# 10_ToSourceBoard.net
KiCad netlist of a schematic drawn in Altium Designer
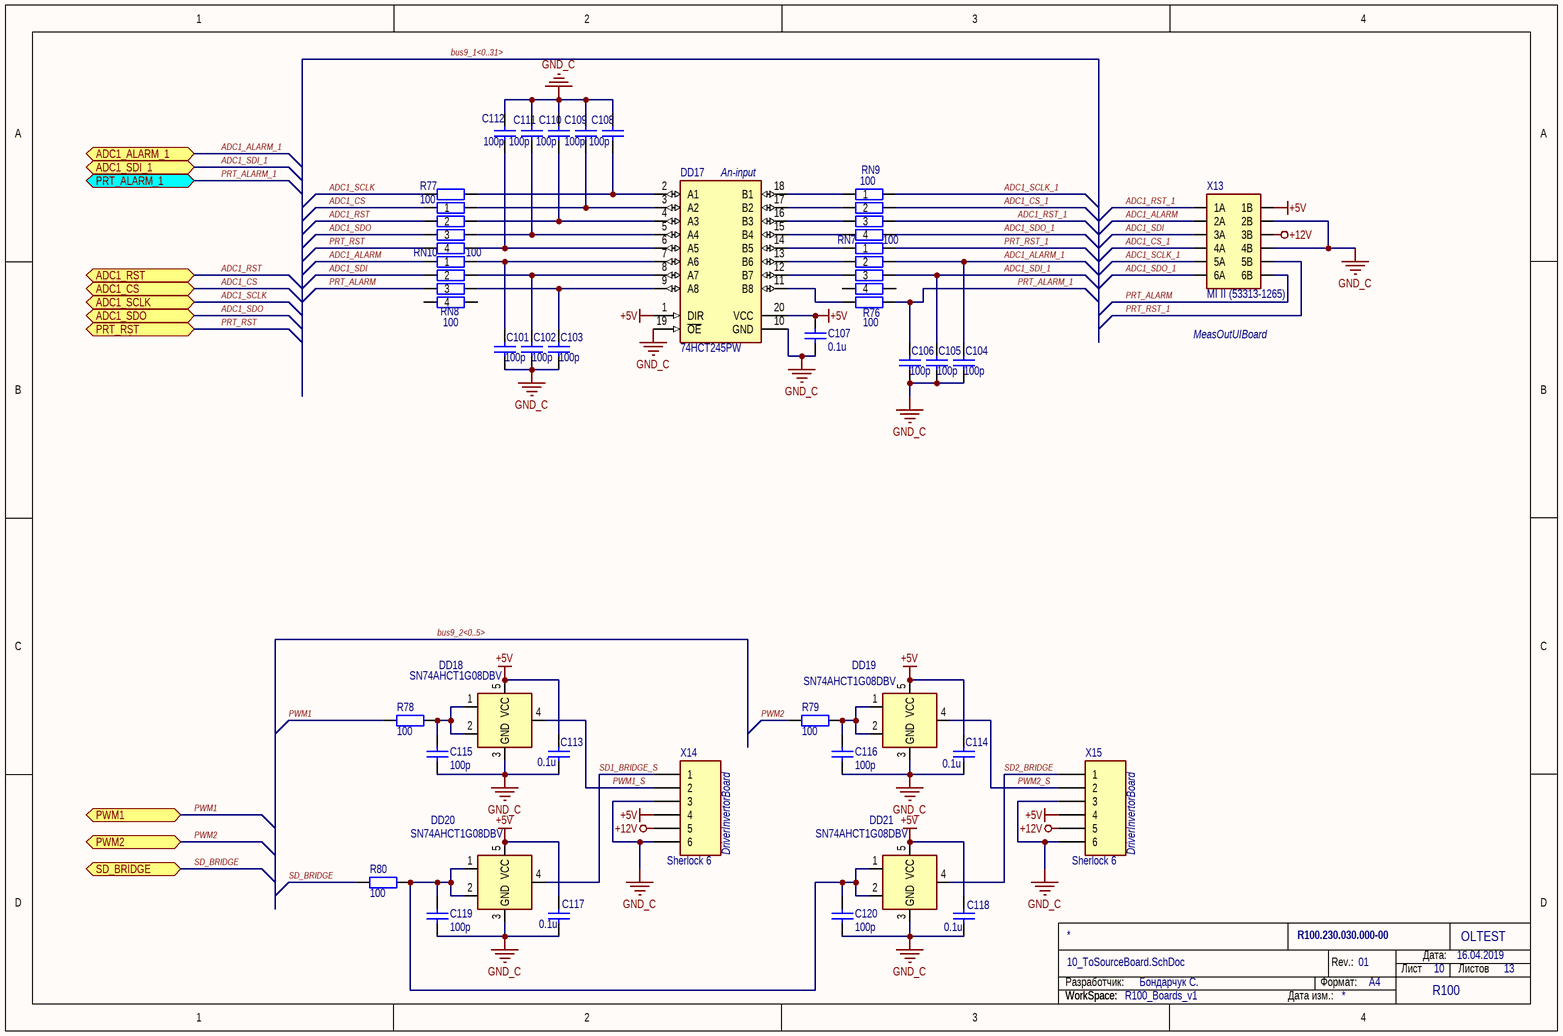
[diagram p0: 10_ToSourceBoard.SchDoc]

(export (version "E")
  (design (tool "Eeschema 10.0.6"))
  (components
    (comp (ref "C101")
      (value "100p")
      (footprint "mainLib:SMD_C_0603")
      (description "SMD C 0603 MURATA 100V 5% NP0")
      (fields (field (name "PARTNUMBER") "GRM1885C2A101JA01") (field (name "MANUFACTURER") "MURATA"))
      (libsource (lib "mainRCLib") (part "C0603 100p 100V 5%"))
    )
    (comp (ref "C102")
      (value "100p")
      (footprint "mainLib:SMD_C_0603")
      (description "SMD C 0603 MURATA 100V 5% NP0")
      (fields (field (name "PARTNUMBER") "GRM1885C2A101JA01") (field (name "MANUFACTURER") "MURATA"))
      (libsource (lib "mainRCLib") (part "C0603 100p 100V 5%"))
    )
    (comp (ref "C103")
      (value "100p")
      (footprint "mainLib:SMD_C_0603")
      (description "SMD C 0603 MURATA 100V 5% NP0")
      (fields (field (name "PARTNUMBER") "GRM1885C2A101JA01") (field (name "MANUFACTURER") "MURATA"))
      (libsource (lib "mainRCLib") (part "C0603 100p 100V 5%"))
    )
    (comp (ref "C104")
      (value "100p")
      (footprint "mainLib:SMD_C_0603")
      (description "SMD C 0603 MURATA 100V 5% NP0")
      (fields (field (name "PARTNUMBER") "GRM1885C2A101JA01") (field (name "MANUFACTURER") "MURATA"))
      (libsource (lib "mainRCLib") (part "C0603 100p 100V 5%"))
    )
    (comp (ref "C105")
      (value "100p")
      (footprint "mainLib:SMD_C_0603")
      (description "SMD C 0603 MURATA 100V 5% NP0")
      (fields (field (name "PARTNUMBER") "GRM1885C2A101JA01") (field (name "MANUFACTURER") "MURATA"))
      (libsource (lib "mainRCLib") (part "C0603 100p 100V 5%"))
    )
    (comp (ref "C106")
      (value "100p")
      (footprint "mainLib:SMD_C_0603")
      (description "SMD C 0603 MURATA 100V 5% NP0")
      (fields (field (name "PARTNUMBER") "GRM1885C2A101JA01") (field (name "MANUFACTURER") "MURATA"))
      (libsource (lib "mainRCLib") (part "C0603 100p 100V 5%"))
    )
    (comp (ref "C107")
      (value "0.1u")
      (footprint "mainLib:SMD_C_0603")
      (description "SMD C 0603 MURATA 50V 10% X7R")
      (fields (field (name "PARTNUMBER") "GRM188R71H104K") (field (name "MANUFACTURER") "MURATA"))
      (libsource (lib "mainRCLib") (part "C0603 0.1u 50V 10%"))
    )
    (comp (ref "C108")
      (value "100p")
      (footprint "mainLib:SMD_C_0603")
      (description "SMD C 0603 MURATA 100V 5% NP0")
      (fields (field (name "PARTNUMBER") "GRM1885C2A101JA01") (field (name "MANUFACTURER") "MURATA"))
      (libsource (lib "mainRCLib") (part "C0603 100p 100V 5%"))
    )
    (comp (ref "C109")
      (value "100p")
      (footprint "mainLib:SMD_C_0603")
      (description "SMD C 0603 MURATA 100V 5% NP0")
      (fields (field (name "PARTNUMBER") "GRM1885C2A101JA01") (field (name "MANUFACTURER") "MURATA"))
      (libsource (lib "mainRCLib") (part "C0603 100p 100V 5%"))
    )
    (comp (ref "C110")
      (value "100p")
      (footprint "mainLib:SMD_C_0603")
      (description "SMD C 0603 MURATA 100V 5% NP0")
      (fields (field (name "PARTNUMBER") "GRM1885C2A101JA01") (field (name "MANUFACTURER") "MURATA"))
      (libsource (lib "mainRCLib") (part "C0603 100p 100V 5%"))
    )
    (comp (ref "C111")
      (value "100p")
      (footprint "mainLib:SMD_C_0603")
      (description "SMD C 0603 MURATA 100V 5% NP0")
      (fields (field (name "PARTNUMBER") "GRM1885C2A101JA01") (field (name "MANUFACTURER") "MURATA"))
      (libsource (lib "mainRCLib") (part "C0603 100p 100V 5%"))
    )
    (comp (ref "C112")
      (value "100p")
      (footprint "mainLib:SMD_C_0603")
      (description "SMD C 0603 MURATA 100V 5% NP0")
      (fields (field (name "PARTNUMBER") "GRM1885C2A101JA01") (field (name "MANUFACTURER") "MURATA"))
      (libsource (lib "mainRCLib") (part "C0603 100p 100V 5%"))
    )
    (comp (ref "C113")
      (value "0.1u")
      (footprint "mainLib:SMD_C_0603")
      (description "SMD C 0603 MURATA 50V 10% X7R")
      (fields (field (name "PARTNUMBER") "GRM188R71H104K") (field (name "MANUFACTURER") "MURATA"))
      (libsource (lib "mainRCLib") (part "C0603 0.1u 50V 10%"))
    )
    (comp (ref "C114")
      (value "0.1u")
      (footprint "mainLib:SMD_C_0603")
      (description "SMD C 0603 MURATA 50V 10% X7R")
      (fields (field (name "PARTNUMBER") "GRM188R71H104K") (field (name "MANUFACTURER") "MURATA"))
      (libsource (lib "mainRCLib") (part "C0603 0.1u 50V 10%"))
    )
    (comp (ref "C115")
      (value "100p")
      (footprint "mainLib:SMD_C_0603")
      (description "SMD C 0603 MURATA 100V 5% NP0")
      (fields (field (name "PARTNUMBER") "GRM1885C2A101JA01") (field (name "MANUFACTURER") "MURATA"))
      (libsource (lib "mainRCLib") (part "C0603 100p 100V 5%"))
    )
    (comp (ref "C116")
      (value "100p")
      (footprint "mainLib:SMD_C_0603")
      (description "SMD C 0603 MURATA 100V 5% NP0")
      (fields (field (name "PARTNUMBER") "GRM1885C2A101JA01") (field (name "MANUFACTURER") "MURATA"))
      (libsource (lib "mainRCLib") (part "C0603 100p 100V 5%"))
    )
    (comp (ref "C117")
      (value "0.1u")
      (footprint "mainLib:SMD_C_0603")
      (description "SMD C 0603 MURATA 50V 10% X7R")
      (fields (field (name "PARTNUMBER") "GRM188R71H104K") (field (name "MANUFACTURER") "MURATA"))
      (libsource (lib "mainRCLib") (part "C0603 0.1u 50V 10%"))
    )
    (comp (ref "C118")
      (value "0.1u")
      (footprint "mainLib:SMD_C_0603")
      (description "SMD C 0603 MURATA 50V 10% X7R")
      (fields (field (name "PARTNUMBER") "GRM188R71H104K") (field (name "MANUFACTURER") "MURATA"))
      (libsource (lib "mainRCLib") (part "C0603 0.1u 50V 10%"))
    )
    (comp (ref "C119")
      (value "100p")
      (footprint "mainLib:SMD_C_0603")
      (description "SMD C 0603 MURATA 100V 5% NP0")
      (fields (field (name "PARTNUMBER") "GRM1885C2A101JA01") (field (name "MANUFACTURER") "MURATA"))
      (libsource (lib "mainRCLib") (part "C0603 100p 100V 5%"))
    )
    (comp (ref "C120")
      (value "100p")
      (footprint "mainLib:SMD_C_0603")
      (description "SMD C 0603 MURATA 100V 5% NP0")
      (fields (field (name "PARTNUMBER") "GRM1885C2A101JA01") (field (name "MANUFACTURER") "MURATA"))
      (libsource (lib "mainRCLib") (part "C0603 100p 100V 5%"))
    )
    (comp (ref "DD17")
      (value "74HCT245PW")
      (footprint "mainLib:PW0020A_M")
      (description "Octal Bus Transceivers With 3-State Outputs, PW0020A")
      (fields (field (name "MANUFACTURER") "NXP"))
      (libsource (lib "mainLib") (part "74HCT245PW"))
    )
    (comp (ref "DD18")
      (value "SN74AHCT1G08DBV")
      (footprint "mainLib:SOT-23(DBV)")
      (description "2-in AND")
      (fields (field (name "MANUFACTURER") "Texas Instruments"))
      (libsource (lib "mainLib") (part "SN74AHCT1G08DBV"))
    )
    (comp (ref "DD19")
      (value "SN74AHCT1G08DBV")
      (footprint "mainLib:SOT-23(DBV)")
      (description "2-in AND")
      (fields (field (name "MANUFACTURER") "Texas Instruments"))
      (libsource (lib "mainLib") (part "SN74AHCT1G08DBV"))
    )
    (comp (ref "DD20")
      (value "SN74AHCT1G08DBV")
      (footprint "mainLib:SOT-23(DBV)")
      (description "2-in AND")
      (fields (field (name "MANUFACTURER") "Texas Instruments"))
      (libsource (lib "mainLib") (part "SN74AHCT1G08DBV"))
    )
    (comp (ref "DD21")
      (value "SN74AHCT1G08DBV")
      (footprint "mainLib:SOT-23(DBV)")
      (description "2-in AND")
      (fields (field (name "MANUFACTURER") "Texas Instruments"))
      (libsource (lib "mainLib") (part "SN74AHCT1G08DBV"))
    )
    (comp (ref "R76")
      (value "100")
      (footprint "SMD_R_0603")
      (description "SMD R 0603 VISHAY 0.1W 75V 1% 100ppm")
      (fields (field (name "PARTNUMBER") "CRCW0603100RFK") (field (name "MANUFACTURER") "VISHAY"))
      (libsource (lib "mainRCLib") (part "R0603 100 1%"))
    )
    (comp (ref "R77")
      (value "100")
      (footprint "SMD_R_0603")
      (description "SMD R 0603 VISHAY 0.1W 75V 1% 100ppm")
      (fields (field (name "PARTNUMBER") "CRCW0603100RFK") (field (name "MANUFACTURER") "VISHAY"))
      (libsource (lib "mainRCLib") (part "R0603 100 1%"))
    )
    (comp (ref "R78")
      (value "100")
      (footprint "SMD_R_0603")
      (description "SMD R 0603 VISHAY 0.1W 75V 1% 100ppm")
      (fields (field (name "PARTNUMBER") "CRCW0603100RFK") (field (name "MANUFACTURER") "VISHAY"))
      (libsource (lib "mainRCLib") (part "R0603 100 1%"))
    )
    (comp (ref "R79")
      (value "100")
      (footprint "SMD_R_0603")
      (description "SMD R 0603 VISHAY 0.1W 75V 1% 100ppm")
      (fields (field (name "PARTNUMBER") "CRCW0603100RFK") (field (name "MANUFACTURER") "VISHAY"))
      (libsource (lib "mainRCLib") (part "R0603 100 1%"))
    )
    (comp (ref "R80")
      (value "100")
      (footprint "SMD_R_0603")
      (description "SMD R 0603 VISHAY 0.1W 75V 1% 100ppm")
      (fields (field (name "PARTNUMBER") "CRCW0603100RFK") (field (name "MANUFACTURER") "VISHAY"))
      (libsource (lib "mainRCLib") (part "R0603 100 1%"))
    )
    (comp (ref "RN7")
      (value "100")
      (footprint "mainLib:CRA06S")
      (description "SMD RESISTOR ARRAY VISHAY 0.063W 50V 1% 100ppm")
      (fields (field (name "PARTNUMBER") "CRA06S083100RF") (field (name "MANUFACTURER") "VISHAY"))
      (libsource (lib "mainRCLib") (part "CRA06S 4x100 1%"))
    )
    (comp (ref "RN8")
      (value "100")
      (footprint "mainLib:CRA06S")
      (description "SMD RESISTOR ARRAY VISHAY 0.063W 50V 1% 100ppm")
      (fields (field (name "PARTNUMBER") "CRA06S083100RF") (field (name "MANUFACTURER") "VISHAY"))
      (libsource (lib "mainRCLib") (part "CRA06S 4x100 1%"))
    )
    (comp (ref "RN9")
      (value "100")
      (footprint "mainLib:CRA06S")
      (description "SMD RESISTOR ARRAY VISHAY 0.063W 50V 1% 100ppm")
      (fields (field (name "PARTNUMBER") "CRA06S083100RF") (field (name "MANUFACTURER") "VISHAY"))
      (libsource (lib "mainRCLib") (part "CRA06S 4x100 1%"))
    )
    (comp (ref "RN10")
      (value "100")
      (footprint "mainLib:CRA06S")
      (description "SMD RESISTOR ARRAY VISHAY 0.063W 50V 1% 100ppm")
      (fields (field (name "PARTNUMBER") "CRA06S083100RF") (field (name "MANUFACTURER") "VISHAY"))
      (libsource (lib "mainRCLib") (part "CRA06S 4x100 1%"))
    )
    (comp (ref "X13")
      (value "MI II (53313-1265)")
      (footprint "mainLib:53313-1265")
      (description "MI II 12 (6x2row), 2A 125V 2mm")
      (fields (field (name "PARTNUMBER") "53313-1265") (field (name "MANUFACTURER") "MOLEX"))
      (libsource (lib "mainLib") (part "53313-1265"))
    )
    (comp (ref "X14")
      (value "Sherlock 6")
      (footprint "mainLib:35362-0650")
      (description "Sherlock 6 Side, 2A 125V 2mm")
      (fields (field (name "PARTNUMBER") "35362-0650") (field (name "MANUFACTURER") "MOLEX"))
      (libsource (lib "mainLib") (part "35363-0650"))
    )
    (comp (ref "X15")
      (value "Sherlock 6")
      (footprint "mainLib:35362-0650")
      (description "Sherlock 6 Side, 2A 125V 2mm")
      (fields (field (name "PARTNUMBER") "35362-0650") (field (name "MANUFACTURER") "MOLEX"))
      (libsource (lib "mainLib") (part "35363-0650"))
    )
  )
  (nets
    (net (code "3") (name "+5V") (class "Default")
      (node (ref "C107") (pin "2") (pinfunction "2_2") (pintype "passive"))
      (node (ref "C113") (pin "2") (pinfunction "2_2") (pintype "passive"))
      (node (ref "C114") (pin "2") (pinfunction "2_2") (pintype "passive"))
      (node (ref "C117") (pin "2") (pinfunction "2_2") (pintype "passive"))
      (node (ref "C118") (pin "2") (pinfunction "2_2") (pintype "passive"))
      (node (ref "DD17") (pin "1") (pinfunction "DIR_1") (pintype "input"))
      (node (ref "DD17") (pin "20") (pinfunction "VCC_20") (pintype "power_in"))
      (node (ref "DD18") (pin "5") (pinfunction "VCC_5") (pintype "passive"))
      (node (ref "DD19") (pin "5") (pinfunction "VCC_5") (pintype "passive"))
      (node (ref "DD20") (pin "5") (pinfunction "VCC_5") (pintype "passive"))
      (node (ref "DD21") (pin "5") (pinfunction "VCC_5") (pintype "passive"))
      (node (ref "X13") (pin "1B") (pinfunction "1B_1B") (pintype "passive"))
      (node (ref "X14") (pin "4") (pinfunction "4_4") (pintype "passive"))
      (node (ref "X15") (pin "4") (pinfunction "4_4") (pintype "passive"))
    )
    (net (code "4") (name "+12V") (class "Default")
      (node (ref "X13") (pin "3B") (pinfunction "3B_3B") (pintype "passive"))
      (node (ref "X14") (pin "5") (pinfunction "5_5") (pintype "passive"))
      (node (ref "X15") (pin "5") (pinfunction "5_5") (pintype "passive"))
    )
    (net (code "5") (name "/ADC1_ALARM") (class "Default")
      (node (ref "RN8") (pin "1") (pinfunction "1_1") (pintype "passive"))
      (node (ref "X13") (pin "2A") (pinfunction "2A_2A") (pintype "passive"))
    )
    (net (code "6") (name "/ADC1_ALARM_1") (class "Default")
      (node (ref "C104") (pin "2") (pinfunction "2_2") (pintype "passive"))
      (node (ref "RN7") (pin "7") (pinfunction "7_7") (pintype "passive"))
    )
    (net (code "7") (name "/ADC1_CS") (class "Default")
      (node (ref "RN10") (pin "1") (pinfunction "1_1") (pintype "passive"))
    )
    (net (code "8") (name "/ADC1_CS_1") (class "Default")
      (node (ref "RN9") (pin "7") (pinfunction "7_7") (pintype "passive"))
      (node (ref "X13") (pin "4A") (pinfunction "4A_4A") (pintype "passive"))
    )
    (net (code "9") (name "/ADC1_RST") (class "Default")
      (node (ref "RN10") (pin "2") (pinfunction "2_2") (pintype "passive"))
    )
    (net (code "10") (name "/ADC1_RST_1") (class "Default")
      (node (ref "RN9") (pin "6") (pinfunction "6_6") (pintype "passive"))
      (node (ref "X13") (pin "1A") (pinfunction "1A_1A") (pintype "passive"))
    )
    (net (code "11") (name "/ADC1_SCLK") (class "Default")
      (node (ref "R77") (pin "1") (pinfunction "1_1") (pintype "passive"))
    )
    (net (code "12") (name "/ADC1_SCLK_1") (class "Default")
      (node (ref "RN9") (pin "8") (pinfunction "8_8") (pintype "passive"))
      (node (ref "X13") (pin "5A") (pinfunction "5A_5A") (pintype "passive"))
    )
    (net (code "13") (name "/ADC1_SDI") (class "Default")
      (node (ref "RN8") (pin "2") (pinfunction "2_2") (pintype "passive"))
      (node (ref "X13") (pin "3A") (pinfunction "3A_3A") (pintype "passive"))
    )
    (net (code "14") (name "/ADC1_SDI_1") (class "Default")
      (node (ref "C105") (pin "2") (pinfunction "2_2") (pintype "passive"))
      (node (ref "RN7") (pin "6") (pinfunction "6_6") (pintype "passive"))
    )
    (net (code "15") (name "/ADC1_SDO") (class "Default")
      (node (ref "RN10") (pin "3") (pinfunction "3_3") (pintype "passive"))
    )
    (net (code "16") (name "/ADC1_SDO_1") (class "Default")
      (node (ref "RN9") (pin "5") (pinfunction "5_5") (pintype "passive"))
      (node (ref "X13") (pin "6A") (pinfunction "6A_6A") (pintype "passive"))
    )
    (net (code "17") (name "/PRT_ALARM") (class "Default")
      (node (ref "RN8") (pin "3") (pinfunction "3_3") (pintype "passive"))
      (node (ref "X13") (pin "6B") (pinfunction "6B_6B") (pintype "passive"))
    )
    (net (code "18") (name "/PRT_ALARM_1") (class "Default")
      (node (ref "C106") (pin "2") (pinfunction "2_2") (pintype "passive"))
      (node (ref "R76") (pin "2") (pinfunction "2_2") (pintype "passive"))
    )
    (net (code "19") (name "/PRT_RST") (class "Default")
      (node (ref "RN10") (pin "4") (pinfunction "4_4") (pintype "passive"))
    )
    (net (code "20") (name "/PRT_RST_1") (class "Default")
      (node (ref "RN7") (pin "8") (pinfunction "8_8") (pintype "passive"))
      (node (ref "X13") (pin "5B") (pinfunction "5B_5B") (pintype "passive"))
    )
    (net (code "21") (name "/PWM1") (class "Default")
      (node (ref "R78") (pin "1") (pinfunction "1_1") (pintype "passive"))
    )
    (net (code "22") (name "/PWM1_S") (class "Default")
      (node (ref "DD18") (pin "4") (pintype "passive"))
      (node (ref "X14") (pin "2") (pinfunction "2_2") (pintype "passive"))
    )
    (net (code "23") (name "/PWM2") (class "Default")
      (node (ref "R79") (pin "1") (pinfunction "1_1") (pintype "passive"))
    )
    (net (code "24") (name "/PWM2_S") (class "Default")
      (node (ref "DD19") (pin "4") (pintype "passive"))
      (node (ref "X15") (pin "2") (pinfunction "2_2") (pintype "passive"))
    )
    (net (code "25") (name "/SD1_BRIDGE_S") (class "Default")
      (node (ref "DD20") (pin "4") (pintype "passive"))
      (node (ref "X14") (pin "1") (pinfunction "1_1") (pintype "passive"))
    )
    (net (code "26") (name "/SD2_BRIDGE") (class "Default")
      (node (ref "DD21") (pin "4") (pintype "passive"))
      (node (ref "X15") (pin "1") (pinfunction "1_1") (pintype "passive"))
    )
    (net (code "27") (name "/SD_BRIDGE") (class "Default")
      (node (ref "R80") (pin "1") (pinfunction "1_1") (pintype "passive"))
    )
    (net (code "30") (name "GND_C") (class "Default")
      (node (ref "C101") (pin "1") (pinfunction "1_1") (pintype "passive"))
      (node (ref "C102") (pin "1") (pinfunction "1_1") (pintype "passive"))
      (node (ref "C103") (pin "1") (pinfunction "1_1") (pintype "passive"))
      (node (ref "C104") (pin "1") (pinfunction "1_1") (pintype "passive"))
      (node (ref "C105") (pin "1") (pinfunction "1_1") (pintype "passive"))
      (node (ref "C106") (pin "1") (pinfunction "1_1") (pintype "passive"))
      (node (ref "C107") (pin "1") (pinfunction "1_1") (pintype "passive"))
      (node (ref "C108") (pin "1") (pinfunction "1_1") (pintype "passive"))
      (node (ref "C109") (pin "1") (pinfunction "1_1") (pintype "passive"))
      (node (ref "C110") (pin "1") (pinfunction "1_1") (pintype "passive"))
      (node (ref "C111") (pin "1") (pinfunction "1_1") (pintype "passive"))
      (node (ref "C112") (pin "1") (pinfunction "1_1") (pintype "passive"))
      (node (ref "C113") (pin "1") (pinfunction "1_1") (pintype "passive"))
      (node (ref "C114") (pin "1") (pinfunction "1_1") (pintype "passive"))
      (node (ref "C115") (pin "1") (pinfunction "1_1") (pintype "passive"))
      (node (ref "C116") (pin "1") (pinfunction "1_1") (pintype "passive"))
      (node (ref "C117") (pin "1") (pinfunction "1_1") (pintype "passive"))
      (node (ref "C118") (pin "1") (pinfunction "1_1") (pintype "passive"))
      (node (ref "C119") (pin "1") (pinfunction "1_1") (pintype "passive"))
      (node (ref "C120") (pin "1") (pinfunction "1_1") (pintype "passive"))
      (node (ref "DD17") (pin "10") (pinfunction "GND_10") (pintype "power_in"))
      (node (ref "DD17") (pin "19") (pinfunction "~{OE}_19") (pintype "input"))
      (node (ref "DD18") (pin "3") (pinfunction "GND_3") (pintype "passive"))
      (node (ref "DD19") (pin "3") (pinfunction "GND_3") (pintype "passive"))
      (node (ref "DD20") (pin "3") (pinfunction "GND_3") (pintype "passive"))
      (node (ref "DD21") (pin "3") (pinfunction "GND_3") (pintype "passive"))
      (node (ref "X13") (pin "2B") (pinfunction "2B_2B") (pintype "passive"))
      (node (ref "X13") (pin "4B") (pinfunction "4B_4B") (pintype "passive"))
      (node (ref "X14") (pin "3") (pinfunction "3_3") (pintype "passive"))
      (node (ref "X14") (pin "6") (pinfunction "6_6") (pintype "passive"))
      (node (ref "X15") (pin "3") (pinfunction "3_3") (pintype "passive"))
      (node (ref "X15") (pin "6") (pinfunction "6_6") (pintype "passive"))
    )
    (net (code "31") (name "Net-(C115-Pad2)") (class "Default")
      (node (ref "C115") (pin "2") (pinfunction "2_2") (pintype "passive"))
      (node (ref "DD18") (pin "1") (pintype "passive"))
      (node (ref "DD18") (pin "2") (pintype "passive"))
      (node (ref "R78") (pin "2") (pinfunction "2_2") (pintype "passive"))
    )
    (net (code "32") (name "Net-(C116-Pad2)") (class "Default")
      (node (ref "C116") (pin "2") (pinfunction "2_2") (pintype "passive"))
      (node (ref "DD19") (pin "1") (pintype "passive"))
      (node (ref "DD19") (pin "2") (pintype "passive"))
      (node (ref "R79") (pin "2") (pinfunction "2_2") (pintype "passive"))
    )
    (net (code "33") (name "Net-(C119-Pad2)") (class "Default")
      (node (ref "C119") (pin "2") (pinfunction "2_2") (pintype "passive"))
      (node (ref "C120") (pin "2") (pinfunction "2_2") (pintype "passive"))
      (node (ref "DD20") (pin "1") (pintype "passive"))
      (node (ref "DD20") (pin "2") (pintype "passive"))
      (node (ref "DD21") (pin "1") (pintype "passive"))
      (node (ref "DD21") (pin "2") (pintype "passive"))
      (node (ref "R80") (pin "2") (pinfunction "2_2") (pintype "passive"))
    )
    (net (code "34") (name "Net-(DD17-A1)") (class "Default")
      (node (ref "C108") (pin "2") (pinfunction "2_2") (pintype "passive"))
      (node (ref "DD17") (pin "2") (pinfunction "A1_2") (pintype "bidirectional"))
      (node (ref "R77") (pin "2") (pinfunction "2_2") (pintype "passive"))
    )
    (net (code "35") (name "Net-(DD17-A2)") (class "Default")
      (node (ref "C109") (pin "2") (pinfunction "2_2") (pintype "passive"))
      (node (ref "DD17") (pin "3") (pinfunction "A2_3") (pintype "bidirectional"))
      (node (ref "RN10") (pin "8") (pinfunction "8_8") (pintype "passive"))
    )
    (net (code "36") (name "Net-(DD17-A3)") (class "Default")
      (node (ref "C110") (pin "2") (pinfunction "2_2") (pintype "passive"))
      (node (ref "DD17") (pin "4") (pinfunction "A3_4") (pintype "bidirectional"))
      (node (ref "RN10") (pin "7") (pinfunction "7_7") (pintype "passive"))
    )
    (net (code "37") (name "Net-(DD17-A4)") (class "Default")
      (node (ref "C111") (pin "2") (pinfunction "2_2") (pintype "passive"))
      (node (ref "DD17") (pin "5") (pinfunction "A4_5") (pintype "bidirectional"))
      (node (ref "RN10") (pin "6") (pinfunction "6_6") (pintype "passive"))
    )
    (net (code "38") (name "Net-(DD17-A5)") (class "Default")
      (node (ref "C112") (pin "2") (pinfunction "2_2") (pintype "passive"))
      (node (ref "DD17") (pin "6") (pinfunction "A5_6") (pintype "bidirectional"))
      (node (ref "RN10") (pin "5") (pinfunction "5_5") (pintype "passive"))
    )
    (net (code "39") (name "Net-(DD17-A6)") (class "Default")
      (node (ref "C101") (pin "2") (pinfunction "2_2") (pintype "passive"))
      (node (ref "DD17") (pin "7") (pinfunction "A6_7") (pintype "bidirectional"))
      (node (ref "RN8") (pin "8") (pinfunction "8_8") (pintype "passive"))
    )
    (net (code "40") (name "Net-(DD17-A7)") (class "Default")
      (node (ref "C102") (pin "2") (pinfunction "2_2") (pintype "passive"))
      (node (ref "DD17") (pin "8") (pinfunction "A7_8") (pintype "bidirectional"))
      (node (ref "RN8") (pin "7") (pinfunction "7_7") (pintype "passive"))
    )
    (net (code "41") (name "Net-(DD17-A8)") (class "Default")
      (node (ref "C103") (pin "2") (pinfunction "2_2") (pintype "passive"))
      (node (ref "DD17") (pin "9") (pinfunction "A8_9") (pintype "bidirectional"))
      (node (ref "RN8") (pin "6") (pinfunction "6_6") (pintype "passive"))
    )
    (net (code "42") (name "Net-(DD17-B1)") (class "Default")
      (node (ref "DD17") (pin "18") (pinfunction "B1_18") (pintype "bidirectional"))
      (node (ref "RN9") (pin "1") (pinfunction "1_1") (pintype "passive"))
    )
    (net (code "43") (name "Net-(DD17-B2)") (class "Default")
      (node (ref "DD17") (pin "17") (pinfunction "B2_17") (pintype "bidirectional"))
      (node (ref "RN9") (pin "2") (pinfunction "2_2") (pintype "passive"))
    )
    (net (code "44") (name "Net-(DD17-B3)") (class "Default")
      (node (ref "DD17") (pin "16") (pinfunction "B3_16") (pintype "bidirectional"))
      (node (ref "RN9") (pin "3") (pinfunction "3_3") (pintype "passive"))
    )
    (net (code "45") (name "Net-(DD17-B4)") (class "Default")
      (node (ref "DD17") (pin "15") (pinfunction "B4_15") (pintype "bidirectional"))
      (node (ref "RN9") (pin "4") (pinfunction "4_4") (pintype "passive"))
    )
    (net (code "46") (name "Net-(DD17-B5)") (class "Default")
      (node (ref "DD17") (pin "14") (pinfunction "B5_14") (pintype "bidirectional"))
      (node (ref "RN7") (pin "1") (pinfunction "1_1") (pintype "passive"))
    )
    (net (code "47") (name "Net-(DD17-B6)") (class "Default")
      (node (ref "DD17") (pin "13") (pinfunction "B6_13") (pintype "bidirectional"))
      (node (ref "RN7") (pin "2") (pinfunction "2_2") (pintype "passive"))
    )
    (net (code "48") (name "Net-(DD17-B7)") (class "Default")
      (node (ref "DD17") (pin "12") (pinfunction "B7_12") (pintype "bidirectional"))
      (node (ref "RN7") (pin "3") (pinfunction "3_3") (pintype "passive"))
    )
    (net (code "49") (name "Net-(DD17-B8)") (class "Default")
      (node (ref "DD17") (pin "11") (pinfunction "B8_11") (pintype "bidirectional"))
      (node (ref "R76") (pin "1") (pinfunction "1_1") (pintype "passive"))
    )
    (net (code "50") (name "unconnected-(RN7-Pad4)") (class "Default")
      (node (ref "RN7") (pin "4") (pinfunction "4_4") (pintype "passive"))
    )
    (net (code "51") (name "unconnected-(RN7-Pad5)") (class "Default")
      (node (ref "RN7") (pin "5") (pinfunction "5_5") (pintype "passive"))
    )
    (net (code "52") (name "unconnected-(RN8-Pad4)") (class "Default")
      (node (ref "RN8") (pin "4") (pinfunction "4_4") (pintype "passive"))
    )
    (net (code "53") (name "unconnected-(RN8-Pad5)") (class "Default")
      (node (ref "RN8") (pin "5") (pinfunction "5_5") (pintype "passive"))
    )
  )
)
